# Clock_WR.net
KiCad netlist of a schematic drawn in Altium Designer
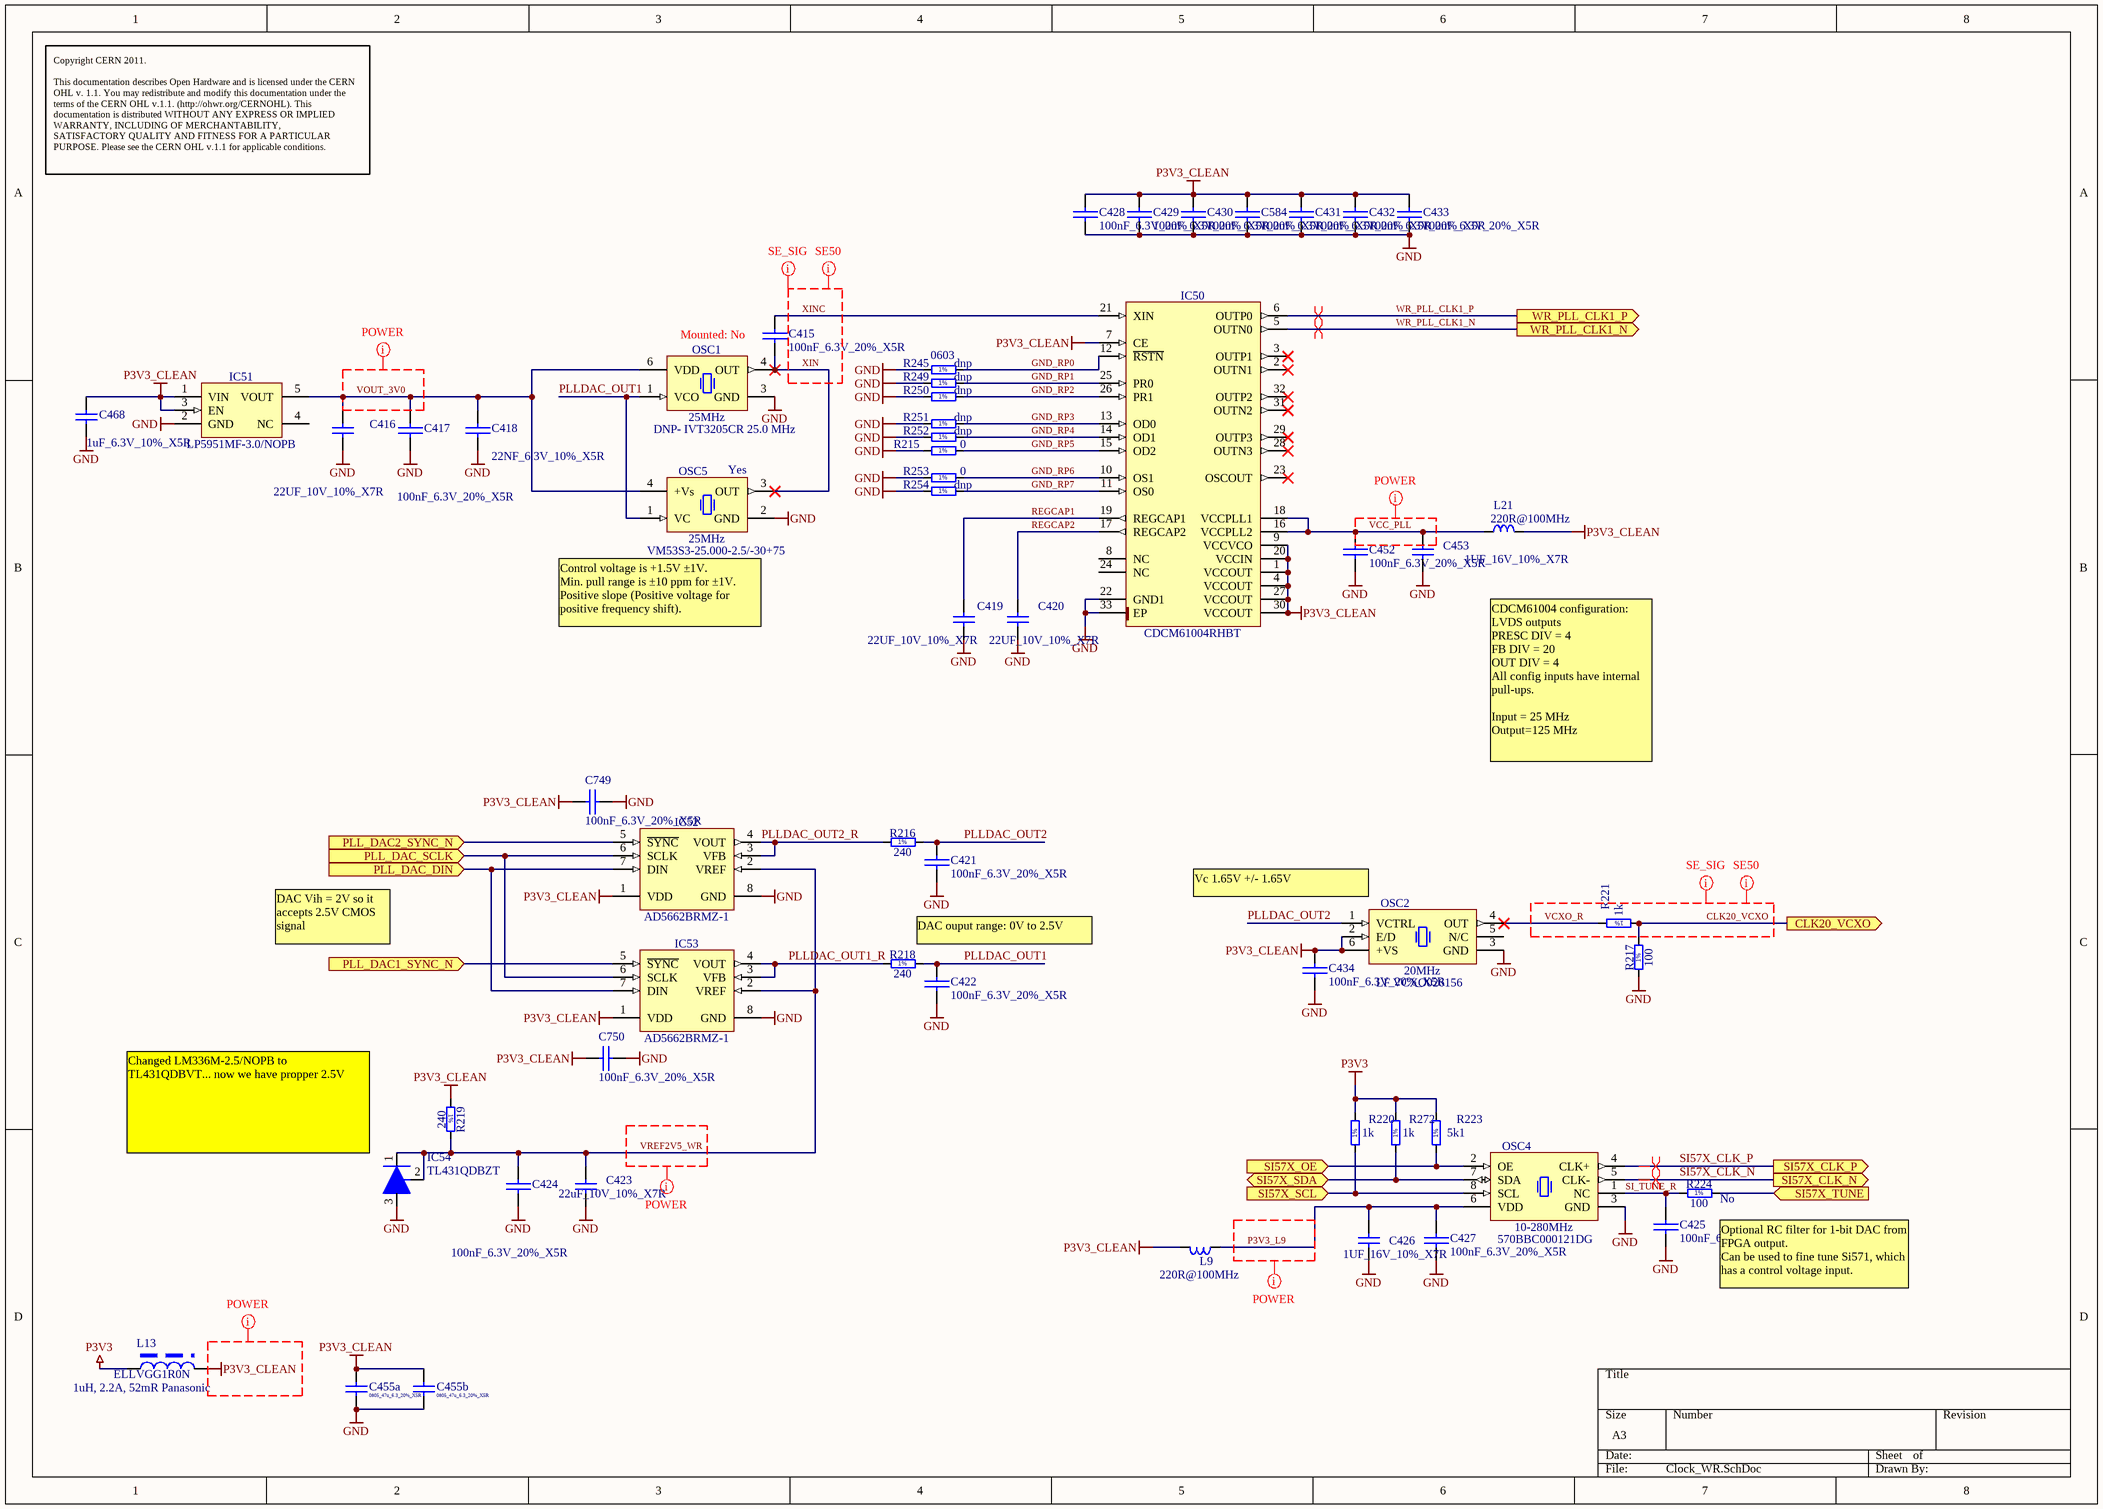
[diagram p0: Clock_WR.SchDoc]

(export (version "E")
  (design (tool "Eeschema 10.0.6"))
  (components
    (comp (ref "C415")
      (value "100nF_6.3V_20%_X5R")
      (footprint "0201C")
      (description "Capacitor SMD")
      (libsource (lib "LIBRARY_SCH") (part "CAP_SMD_0201"))
    )
    (comp (ref "C416")
      (value "22UF_10V_10%_X7R")
      (footprint "CAPC1608X87N")
      (description "Non-polarised capacitor")
      (fields
        (field (name "PART NUMBER") "CC0603_1UF_16V_10%_X7R")
        (field (name "VOLTAGE") "16V")
        (field (name "AUTHOR") "CERN DEM JLC")
      )
      (libsource (lib "Capacitors") (part "Capacitor - non polarized"))
    )
    (comp (ref "C417")
      (value "100nF_6.3V_20%_X5R")
      (footprint "0201C")
      (description "Capacitor SMD")
      (libsource (lib "LIBRARY_SCH") (part "CAP_SMD_0201"))
    )
    (comp (ref "C418")
      (value "22NF_6.3V_10%_X5R")
      (footprint "0201C")
      (description "Capacitor SMD")
      (libsource (lib "LIBRARY_SCH") (part "CAP_SMD_0201"))
    )
    (comp (ref "C419")
      (value "22UF_10V_10%_X7R")
      (footprint "CAPC3216X180N")
      (description "Non-polarised capacitor")
      (fields
        (field (name "PART NUMBER") "CC1206_22UF_10V_10%_X7R")
        (field (name "VOLTAGE") "10V")
        (field (name "AUTHOR") "CERN DEM JLC")
      )
      (libsource (lib "Capacitors") (part "Capacitor - non polarized"))
    )
    (comp (ref "C420")
      (value "22UF_10V_10%_X7R")
      (footprint "CAPC3216X180N")
      (description "Non-polarised capacitor")
      (fields
        (field (name "PART NUMBER") "CC1206_22UF_10V_10%_X7R")
        (field (name "VOLTAGE") "10V")
        (field (name "AUTHOR") "CERN DEM JLC")
      )
      (libsource (lib "Capacitors") (part "Capacitor - non polarized"))
    )
    (comp (ref "C421")
      (value "100nF_6.3V_20%_X5R")
      (footprint "0201C")
      (description "Capacitor SMD")
      (libsource (lib "LIBRARY_SCH") (part "CAP_SMD_0201"))
    )
    (comp (ref "C422")
      (value "100nF_6.3V_20%_X5R")
      (footprint "0201C")
      (description "Capacitor SMD")
      (libsource (lib "LIBRARY_SCH") (part "CAP_SMD_0201"))
    )
    (comp (ref "C423")
      (value "22uF_10V_10%_X7R")
      (footprint "CAPC3216X180N")
      (description "Non-polarised capacitor")
      (fields
        (field (name "PART NUMBER") "CC1206_22UF_10V_10%_X7R")
        (field (name "VOLTAGE") "10V")
        (field (name "AUTHOR") "CERN DEM JLC")
      )
      (libsource (lib "Capacitors") (part "Capacitor - non polarized"))
    )
    (comp (ref "C424")
      (value "100nF_6.3V_20%_X5R")
      (footprint "0201C")
      (description "Capacitor SMD")
      (libsource (lib "LIBRARY_SCH") (part "CAP_SMD_0201"))
    )
    (comp (ref "C425")
      (value "100nF_6.3V_20%_X5R")
      (footprint "0201C")
      (description "Capacitor SMD")
      (libsource (lib "LIBRARY_SCH") (part "CAP_SMD_0201"))
    )
    (comp (ref "C426")
      (value "1UF_16V_10%_X7R")
      (footprint "CAPC1608X87N")
      (description "Non-polarised capacitor")
      (fields
        (field (name "PART NUMBER") "CC0603_1UF_16V_10%_X7R")
        (field (name "VOLTAGE") "16V")
        (field (name "AUTHOR") "CERN DEM JLC")
      )
      (libsource (lib "Capacitors") (part "Capacitor - non polarized"))
    )
    (comp (ref "C427")
      (value "100nF_6.3V_20%_X5R")
      (footprint "0201C")
      (description "Capacitor SMD")
      (libsource (lib "LIBRARY_SCH") (part "CAP_SMD_0201"))
    )
    (comp (ref "C428")
      (value "100nF_6.3V_20%_X5R")
      (footprint "0201C")
      (description "Capacitor SMD")
      (libsource (lib "LIBRARY_SCH") (part "CAP_SMD_0201"))
    )
    (comp (ref "C429")
      (value "100nF_6.3V_20%_X5R")
      (footprint "0201C")
      (description "Capacitor SMD")
      (libsource (lib "LIBRARY_SCH") (part "CAP_SMD_0201"))
    )
    (comp (ref "C430")
      (value "100nF_6.3V_20%_X5R")
      (footprint "0201C")
      (description "Capacitor SMD")
      (libsource (lib "LIBRARY_SCH") (part "CAP_SMD_0201"))
    )
    (comp (ref "C431")
      (value "100nF_6.3V_20%_X5R")
      (footprint "0201C")
      (description "Capacitor SMD")
      (libsource (lib "LIBRARY_SCH") (part "CAP_SMD_0201"))
    )
    (comp (ref "C432")
      (value "100nF_6.3V_20%_X5R")
      (footprint "0201C")
      (description "Capacitor SMD")
      (libsource (lib "LIBRARY_SCH") (part "CAP_SMD_0201"))
    )
    (comp (ref "C433")
      (value "100nF_6.3V_20%_X5R")
      (footprint "0201C")
      (description "Capacitor SMD")
      (libsource (lib "LIBRARY_SCH") (part "CAP_SMD_0201"))
    )
    (comp (ref "C434")
      (value "100nF_6.3V_20%_X5R")
      (footprint "0201C")
      (description "Capacitor SMD")
      (libsource (lib "LIBRARY_SCH") (part "CAP_SMD_0201"))
    )
    (comp (ref "C452")
      (value "100nF_6.3V_20%_X5R")
      (footprint "0201C")
      (description "Capacitor SMD")
      (libsource (lib "LIBRARY_SCH") (part "CAP_SMD_0201"))
    )
    (comp (ref "C453")
      (value "1UF_16V_10%_X7R")
      (footprint "CAPC1608X87N")
      (description "Non-polarised capacitor")
      (fields
        (field (name "PART NUMBER") "CC0603_1UF_16V_10%_X7R")
        (field (name "VOLTAGE") "16V")
        (field (name "AUTHOR") "CERN DEM JLC")
      )
      (libsource (lib "Capacitors") (part "Capacitor - non polarized"))
    )
    (comp (ref "C455a")
      (value "0805_47u_6.3_20%_X5R")
      (footprint "CAPC2012X140N")
      (fields (field (name "PART NUMBER") "Ceramic_0805"))
      (libsource (lib "Capacitors") (part "Capacitor"))
    )
    (comp (ref "C455b")
      (value "0805_47u_6.3_20%_X5R")
      (footprint "CAPC2012X140N")
      (fields (field (name "PART NUMBER") "Ceramic_0805"))
      (libsource (lib "Capacitors") (part "Capacitor"))
    )
    (comp (ref "C468")
      (value "1uF_6.3V_10%_X5R")
      (footprint "CAPC1608X87N")
      (description "Non-polarised capacitor")
      (fields
        (field (name "PART NUMBER") "CC0603_1UF_16V_10%_X7R")
        (field (name "VOLTAGE") "16V")
        (field (name "AUTHOR") "CERN DEM JLC")
      )
      (libsource (lib "Capacitors") (part "Capacitor - non polarized"))
    )
    (comp (ref "C584")
      (value "100nF_6.3V_20%_X5R")
      (footprint "0201C")
      (description "Capacitor SMD")
      (libsource (lib "LIBRARY_SCH") (part "CAP_SMD_0201"))
    )
    (comp (ref "C749")
      (value "100nF_6.3V_20%_X5R")
      (footprint "0201C")
      (description "Capacitor SMD")
      (libsource (lib "LIBRARY_SCH") (part "CAP_SMD_0201"))
    )
    (comp (ref "C750")
      (value "100nF_6.3V_20%_X5R")
      (footprint "0201C")
      (description "Capacitor SMD")
      (libsource (lib "LIBRARY_SCH") (part "CAP_SMD_0201"))
    )
    (comp (ref "IC50")
      (value "CDCM61004RHBT")
      (footprint "QFN50P500X500X100-33N-S355")
      (description "Four Output, Integrated VCO, Low-Jitter Clock Generator")
      (fields (field (name "MANUFACTURER") "TEXAS INSTRUMENTS") (field (name "AUTHOR") "CERN DEM JLC"))
      (libsource (lib "ICs And Semiconductors") (part "CDCM61004RHB"))
    )
    (comp (ref "IC51")
      (value "LP5951MF-3.0/NOPB")
      (footprint "SOT95P284X122-5N")
      (description "150mA Micropower Low-Dropout CMOS Voltage Regulator")
      (fields (field (name "MANUFACTURER") "NATIONAL SEMICONDUCTOR") (field (name "AUTHOR") "CERN DEM JLC"))
      (libsource (lib "ICs And Semiconductors") (part "LP5951"))
    )
    (comp (ref "IC52")
      (value "AD5662BRMZ-1")
      (footprint "SOP65P490X110-8N")
      (description "2.7V to 5.5V, 250uA, Rail-to-Rail Output 16-Bit nanoDAC")
      (fields (field (name "MANUFACTURER") "ANALOG DEVICES") (field (name "AUTHOR") "CERN DEM JLC"))
      (libsource (lib "ICs And Semiconductors") (part "AD5662"))
    )
    (comp (ref "IC53")
      (value "AD5662BRMZ-1")
      (footprint "SOP65P490X110-8N")
      (description "2.7V to 5.5V, 250uA, Rail-to-Rail Output 16-Bit nanoDAC")
      (fields (field (name "MANUFACTURER") "ANALOG DEVICES") (field (name "AUTHOR") "CERN DEM JLC"))
      (libsource (lib "ICs And Semiconductors") (part "AD5662"))
    )
    (comp (ref "IC54")
      (value "TL431QDBZT")
      (footprint "SOT-23")
      (description "2.5V ADJ Voltage reference")
      (libsource (lib "LIBRARY_SCH") (part "REF_TL431_SOT23"))
    )
    (comp (ref "L9")
      (value "220R@100MHz")
      (footprint "INDC2012X105N")
      (description "Inductor")
      (fields
        (field (name "PART NUMBER") "IND0805_MURATA_BLM21PG221SN1D")
        (field (name "POWER") "2A")
        (field (name "AUTHOR") "CERN DEM JLC")
      )
      (libsource (lib "Inductors & Transformers") (part "Inductor"))
    )
    (comp (ref "L13")
      (value "ELLVGG1R0N")
      (footprint "L_ELLVGG2R2N")
      (description "2.2uH, 1.4A, 92mR Panasonic")
      (fields (field (name "ALTIUM_UNNAMED_1") "1uH, 2.2A, 52mR Panasonic"))
      (libsource (lib "LIBRARY_SCH") (part "L_CHOKE_ELLVGG"))
    )
    (comp (ref "L21")
      (value "220R@100MHz")
      (footprint "INDC2012X105N")
      (description "Inductor")
      (fields
        (field (name "PART NUMBER") "IND0805_MURATA_BLM21PG221SN1D")
        (field (name "POWER") "2A")
        (field (name "AUTHOR") "CERN DEM JLC")
      )
      (libsource (lib "Inductors & Transformers") (part "Inductor"))
    )
    (comp (ref "OSC1")
      (value "25MHz")
      (footprint "OSC_RAKON_IVT3200C")
      (description "Oscillator 4 pins 1=VCO 3=GND 4=OUT 6=VDC")
      (fields
        (field (name "PART NUMBER") "OSC_25MHZ_RAKON_IVT3205CR")
        (field (name "MANUFACTURER") "RAKON")
        (field (name "MANUFACTURER PART NUMBER") "DNP- IVT3205CR 25.0 MHz")
        (field (name "MOUNTED") "No")
        (field (name "AUTHOR") "CERN DEM JLC")
      )
      (libsource (lib "ICs And Semiconductors") (part "Oscillator 1VCO 3GND 4OUT 6VCC"))
    )
    (comp (ref "OSC2")
      (value "20MHz")
      (footprint "OSC_IQD_CFPV-45")
      (description "3.3V ±100ppm 15pF HCMOS Tri-State Surface Mount Voltage Controlled Oscillator VCXO (CFPV-45 Serie)")
      (fields
        (field (name "PART NUMBER") "OSC_20MHZ_IQD_LF VCXO026156")
        (field (name "MANUFACTURER") "IQD FREQUENCY PRODUCTS")
        (field (name "MANUFACTURER PART NUMBER") "LF VCXO026156")
        (field (name "AUTHOR") "CERN DEM JLC")
      )
      (libsource (lib "ICs And Semiconductors") (part "Oscillator IQD_CFPV-45"))
    )
    (comp (ref "OSC4")
      (value "10-280MHz")
      (footprint "OSC_SILICON-LAB_SI570")
      (description "Any-Rate I2C Programmable XO Oscillator Si570 Serie")
      (fields
        (field (name "PART NUMBER") "OSC_10-280MHZ_SILICON-LAB_Si570BBC000121DG")
        (field (name "MANUFACTURER") "SILICON LABS")
        (field (name "MANUFACTURER PART NUMBER") "570BBC000121DG")
        (field (name "AUTHOR") "CERN DEM JLC")
      )
      (libsource (lib "ICs And Semiconductors") (part "Oscillator SILICON-LAB_Si570"))
    )
    (comp (ref "OSC5")
      (value "25MHz")
      (footprint "OSCCC320X500X160-4N")
      (description "Oscillator 4 pins 1=VC 2=GND 3=OUT 4=+Vs")
      (fields
        (field (name "PART NUMBER") "OSC_25MHZ_MERCURY_VM53S3-25.000-2.5/-30+75")
        (field (name "MANUFACTURER") "MERCURY ELECTRONICS")
        (field (name "MANUFACTURER PART NUMBER") "VM53S3-25.000-2.5/-30+75")
        (field (name "MOUNTED") "Yes")
        (field (name "AUTHOR") "CERN DEM JLC")
      )
      (libsource (lib "ICs And Semiconductors") (part "Oscillator 1VC 2GND 3OUT 4+Vs"))
    )
    (comp (ref "R215")
      (value "0")
      (footprint "RESC1608X55N")
      (description "Resistor - 1%")
      (fields
        (field (name "PART NUMBER") "R0603_0R_JUMPER")
        (field (name "MANUFACTURER") "GENERIC")
        (field (name "AUTHOR") "CERN DEM JLC")
      )
      (libsource (lib "Resistors") (part "Resistor - 1%"))
    )
    (comp (ref "R216")
      (value "240")
      (footprint "RESC1608X55N")
      (description "Resistor - 1%")
      (fields
        (field (name "PART NUMBER") "R0603_240R_1%_0.1W_100PPM")
        (field (name "POWER") "0.1W")
        (field (name "AUTHOR") "CERN DEM JLC")
      )
      (libsource (lib "Resistors") (part "Resistor - 1%"))
    )
    (comp (ref "R217")
      (value "100")
      (footprint "RESC1608X55N")
      (description "Resistor - 1%")
      (fields
        (field (name "PART NUMBER") "R0603_100R_1%_0.1W_100PPM")
        (field (name "POWER") "0.1W")
        (field (name "AUTHOR") "CERN DEM JLC")
      )
      (libsource (lib "Resistors") (part "Resistor - 1%"))
    )
    (comp (ref "R218")
      (value "240")
      (footprint "RESC1608X55N")
      (description "Resistor - 1%")
      (fields
        (field (name "PART NUMBER") "R0603_240R_1%_0.1W_100PPM")
        (field (name "POWER") "0.1W")
        (field (name "AUTHOR") "CERN DEM JLC")
      )
      (libsource (lib "Resistors") (part "Resistor - 1%"))
    )
    (comp (ref "R219")
      (value "240")
      (footprint "RESC1608X55N")
      (description "Resistor - 1%")
      (fields
        (field (name "PART NUMBER") "R0603_240R_1%_0.1W_100PPM")
        (field (name "POWER") "0.1W")
        (field (name "AUTHOR") "CERN DEM JLC")
      )
      (libsource (lib "Resistors") (part "Resistor - 1%"))
    )
    (comp (ref "R220")
      (value "1k")
      (footprint "RESC1608X55N")
      (description "Resistor - 1%")
      (fields
        (field (name "PART NUMBER") "R0603_1K_1%_0.1W_100PPM")
        (field (name "POWER") "0.1W")
        (field (name "AUTHOR") "CERN DEM JLC")
      )
      (libsource (lib "Resistors") (part "Resistor - 1%"))
    )
    (comp (ref "R221")
      (value "1k")
      (footprint "RESC1608X55N")
      (description "Resistor - 1%")
      (fields
        (field (name "PART NUMBER") "R0603_1K_1%_0.1W_100PPM")
        (field (name "POWER") "0.1W")
        (field (name "AUTHOR") "CERN DEM JLC")
      )
      (libsource (lib "Resistors") (part "Resistor - 1%"))
    )
    (comp (ref "R223")
      (value "5k1")
      (footprint "RESC1608X55N")
      (description "Resistor - 1%")
      (fields
        (field (name "PART NUMBER") "R0603_5K1_1%_0.1W_100PPM")
        (field (name "POWER") "0.1W")
        (field (name "AUTHOR") "CERN DEM JLC")
      )
      (libsource (lib "Resistors") (part "Resistor - 1%"))
    )
    (comp (ref "R224")
      (value "100")
      (footprint "RESC1608X55N")
      (description "Resistor - 1%")
      (fields
        (field (name "PART NUMBER") "R0603_100R_1%_0.1W_100PPM")
        (field (name "POWER") "0.1W")
        (field (name "MOUNTED") "No")
        (field (name "AUTHOR") "CERN DEM JLC")
      )
      (libsource (lib "Resistors") (part "Resistor - 1%"))
    )
    (comp (ref "R245")
      (value "dnp")
      (footprint "RESC1608X55N")
      (description "Resistor - 1%")
      (fields
        (field (name "PART NUMBER") "R0603_0R_JUMPER")
        (field (name "MANUFACTURER") "GENERIC")
        (field (name "CASE") "0603")
        (field (name "AUTHOR") "CERN DEM JLC")
      )
      (libsource (lib "Resistors") (part "Resistor - 1%"))
    )
    (comp (ref "R249")
      (value "dnp")
      (footprint "RESC1608X55N")
      (description "Resistor - 1%")
      (fields
        (field (name "PART NUMBER") "R0603_0R_JUMPER")
        (field (name "MANUFACTURER") "GENERIC")
        (field (name "AUTHOR") "CERN DEM JLC")
      )
      (libsource (lib "Resistors") (part "Resistor - 1%"))
    )
    (comp (ref "R250")
      (value "dnp")
      (footprint "RESC1608X55N")
      (description "Resistor - 1%")
      (fields
        (field (name "PART NUMBER") "R0603_0R_JUMPER")
        (field (name "MANUFACTURER") "GENERIC")
        (field (name "AUTHOR") "CERN DEM JLC")
      )
      (libsource (lib "Resistors") (part "Resistor - 1%"))
    )
    (comp (ref "R251")
      (value "dnp")
      (footprint "RESC1608X55N")
      (description "Resistor - 1%")
      (fields
        (field (name "PART NUMBER") "R0603_0R_JUMPER")
        (field (name "MANUFACTURER") "GENERIC")
        (field (name "AUTHOR") "CERN DEM JLC")
      )
      (libsource (lib "Resistors") (part "Resistor - 1%"))
    )
    (comp (ref "R252")
      (value "dnp")
      (footprint "RESC1608X55N")
      (description "Resistor - 1%")
      (fields
        (field (name "PART NUMBER") "R0603_0R_JUMPER")
        (field (name "MANUFACTURER") "GENERIC")
        (field (name "AUTHOR") "CERN DEM JLC")
      )
      (libsource (lib "Resistors") (part "Resistor - 1%"))
    )
    (comp (ref "R253")
      (value "0")
      (footprint "RESC1608X55N")
      (description "Resistor - 1%")
      (fields
        (field (name "PART NUMBER") "R0603_0R_JUMPER")
        (field (name "MANUFACTURER") "GENERIC")
        (field (name "AUTHOR") "CERN DEM JLC")
      )
      (libsource (lib "Resistors") (part "Resistor - 1%"))
    )
    (comp (ref "R254")
      (value "dnp")
      (footprint "RESC1608X55N")
      (description "Resistor - 1%")
      (fields
        (field (name "PART NUMBER") "R0603_0R_JUMPER")
        (field (name "MANUFACTURER") "GENERIC")
        (field (name "AUTHOR") "CERN DEM JLC")
      )
      (libsource (lib "Resistors") (part "Resistor - 1%"))
    )
    (comp (ref "R272")
      (value "1k")
      (footprint "RESC1608X55N")
      (description "Resistor - 1%")
      (fields
        (field (name "PART NUMBER") "R0603_1K_1%_0.1W_100PPM")
        (field (name "POWER") "0.1W")
        (field (name "AUTHOR") "CERN DEM JLC")
      )
      (libsource (lib "Resistors") (part "Resistor - 1%"))
    )
  )
  (nets
    (net (code "1") (name "/CLK20_VCXO") (class "Default")
      (node (ref "R217") (pin "2") (pinfunction "2_2") (pintype "passive"))
      (node (ref "R221") (pin "1") (pinfunction "1_1") (pintype "passive"))
    )
    (net (code "2") (name "/GND_RP0") (class "Default")
      (node (ref "IC50") (pin "12") (pinfunction "~{RSTN}_12") (pintype "input"))
      (node (ref "R245") (pin "2") (pinfunction "2_2") (pintype "passive"))
    )
    (net (code "3") (name "/GND_RP1") (class "Default")
      (node (ref "IC50") (pin "25") (pinfunction "PR0_25") (pintype "input"))
      (node (ref "R249") (pin "2") (pinfunction "2_2") (pintype "passive"))
    )
    (net (code "4") (name "/GND_RP2") (class "Default")
      (node (ref "IC50") (pin "26") (pinfunction "PR1_26") (pintype "input"))
      (node (ref "R250") (pin "2") (pinfunction "2_2") (pintype "passive"))
    )
    (net (code "5") (name "/GND_RP3") (class "Default")
      (node (ref "IC50") (pin "13") (pinfunction "OD0_13") (pintype "input"))
      (node (ref "R251") (pin "2") (pinfunction "2_2") (pintype "passive"))
    )
    (net (code "6") (name "/GND_RP4") (class "Default")
      (node (ref "IC50") (pin "14") (pinfunction "OD1_14") (pintype "input"))
      (node (ref "R252") (pin "2") (pinfunction "2_2") (pintype "passive"))
    )
    (net (code "7") (name "/GND_RP5") (class "Default")
      (node (ref "IC50") (pin "15") (pinfunction "OD2_15") (pintype "input"))
      (node (ref "R215") (pin "2") (pinfunction "2_2") (pintype "passive"))
    )
    (net (code "8") (name "/GND_RP6") (class "Default")
      (node (ref "IC50") (pin "10") (pinfunction "OS1_10") (pintype "input"))
      (node (ref "R253") (pin "2") (pinfunction "2_2") (pintype "passive"))
    )
    (net (code "9") (name "/GND_RP7") (class "Default")
      (node (ref "IC50") (pin "11") (pinfunction "OS0_11") (pintype "input"))
      (node (ref "R254") (pin "2") (pinfunction "2_2") (pintype "passive"))
    )
    (net (code "10") (name "/P3V3_L9") (class "Default")
      (node (ref "C426") (pin "2") (pinfunction "2_2") (pintype "passive"))
      (node (ref "C427") (pin "1") (pinfunction "1_1") (pintype "passive"))
      (node (ref "L9") (pin "1") (pinfunction "1_1") (pintype "passive"))
      (node (ref "OSC4") (pin "6") (pinfunction "VDD_6") (pintype "power_in"))
    )
    (net (code "11") (name "/PLLDAC_OUT1") (class "Default")
      (node (ref "C422") (pin "1") (pinfunction "1_1") (pintype "passive"))
      (node (ref "OSC1") (pin "1") (pinfunction "VCO_1") (pintype "input"))
      (node (ref "OSC5") (pin "1") (pinfunction "VC_1") (pintype "input"))
      (node (ref "R218") (pin "2") (pinfunction "2_2") (pintype "passive"))
    )
    (net (code "12") (name "/PLLDAC_OUT1_R") (class "Default")
      (node (ref "IC53") (pin "3") (pinfunction "VFB_3") (pintype "input"))
      (node (ref "IC53") (pin "4") (pinfunction "VOUT_4") (pintype "output"))
      (node (ref "R218") (pin "1") (pinfunction "1_1") (pintype "passive"))
    )
    (net (code "13") (name "/PLLDAC_OUT2") (class "Default")
      (node (ref "C421") (pin "1") (pinfunction "1_1") (pintype "passive"))
      (node (ref "OSC2") (pin "1") (pinfunction "VCTRL_1") (pintype "input"))
      (node (ref "R216") (pin "2") (pinfunction "2_2") (pintype "passive"))
    )
    (net (code "14") (name "/PLLDAC_OUT2_R") (class "Default")
      (node (ref "IC52") (pin "3") (pinfunction "VFB_3") (pintype "input"))
      (node (ref "IC52") (pin "4") (pinfunction "VOUT_4") (pintype "output"))
      (node (ref "R216") (pin "1") (pinfunction "1_1") (pintype "passive"))
    )
    (net (code "15") (name "/PLL_DAC1_SYNC_N") (class "Default")
      (node (ref "IC53") (pin "5") (pinfunction "~{SYNC}_5") (pintype "input"))
    )
    (net (code "16") (name "/PLL_DAC2_SYNC_N") (class "Default")
      (node (ref "IC52") (pin "5") (pinfunction "~{SYNC}_5") (pintype "input"))
    )
    (net (code "17") (name "/PLL_DAC_DIN") (class "Default")
      (node (ref "IC52") (pin "7") (pinfunction "DIN_7") (pintype "input"))
      (node (ref "IC53") (pin "7") (pinfunction "DIN_7") (pintype "input"))
    )
    (net (code "18") (name "/PLL_DAC_SCLK") (class "Default")
      (node (ref "IC52") (pin "6") (pinfunction "SCLK_6") (pintype "input"))
      (node (ref "IC53") (pin "6") (pinfunction "SCLK_6") (pintype "input"))
    )
    (net (code "19") (name "/REGCAP1") (class "Default")
      (node (ref "C419") (pin "2") (pinfunction "2_2") (pintype "passive"))
      (node (ref "IC50") (pin "19") (pinfunction "REGCAP1_19") (pintype "output"))
    )
    (net (code "20") (name "/REGCAP2") (class "Default")
      (node (ref "C420") (pin "2") (pinfunction "2_2") (pintype "passive"))
      (node (ref "IC50") (pin "17") (pinfunction "REGCAP2_17") (pintype "output"))
    )
    (net (code "21") (name "/SI57X_CLK_N") (class "Default")
      (node (ref "OSC4") (pin "5") (pinfunction "CLK-_5") (pintype "output"))
    )
    (net (code "22") (name "/SI57X_CLK_P") (class "Default")
      (node (ref "OSC4") (pin "4") (pinfunction "CLK+_4") (pintype "output"))
    )
    (net (code "23") (name "/SI57X_OE") (class "Default")
      (node (ref "OSC4") (pin "2") (pinfunction "OE_2") (pintype "input"))
      (node (ref "R223") (pin "1") (pinfunction "1_1") (pintype "passive"))
    )
    (net (code "24") (name "/SI57X_SCL") (class "Default")
      (node (ref "OSC4") (pin "8") (pinfunction "SCL_8") (pintype "input"))
      (node (ref "R220") (pin "1") (pinfunction "1_1") (pintype "passive"))
    )
    (net (code "25") (name "/SI57X_SDA") (class "Default")
      (node (ref "OSC4") (pin "7") (pinfunction "SDA_7") (pintype "bidirectional"))
      (node (ref "R272") (pin "1") (pinfunction "1_1") (pintype "passive"))
    )
    (net (code "26") (name "/SI57X_TUNE") (class "Default")
      (node (ref "R224") (pin "2") (pinfunction "2_2") (pintype "passive"))
    )
    (net (code "27") (name "/SI_TUNE_R") (class "Default")
      (node (ref "C425") (pin "1") (pinfunction "1_1") (pintype "passive"))
      (node (ref "OSC4") (pin "1") (pinfunction "NC_1") (pintype "passive"))
      (node (ref "R224") (pin "1") (pinfunction "1_1") (pintype "passive"))
    )
    (net (code "28") (name "/VCC_PLL") (class "Default")
      (node (ref "C452") (pin "1") (pinfunction "1_1") (pintype "passive"))
      (node (ref "C453") (pin "2") (pinfunction "2_2") (pintype "passive"))
      (node (ref "IC50") (pin "16") (pinfunction "VCCPLL2_16") (pintype "power_in"))
      (node (ref "IC50") (pin "18") (pinfunction "VCCPLL1_18") (pintype "power_in"))
      (node (ref "L21") (pin "1") (pinfunction "1_1") (pintype "passive"))
    )
    (net (code "29") (name "/VCXO_R") (class "Default")
      (node (ref "OSC2") (pin "4") (pinfunction "OUT_4") (pintype "output"))
      (node (ref "R221") (pin "2") (pinfunction "2_2") (pintype "passive"))
    )
    (net (code "30") (name "/VOUT_3V0") (class "Default")
      (node (ref "C416") (pin "2") (pinfunction "2_2") (pintype "passive"))
      (node (ref "C417") (pin "1") (pinfunction "1_1") (pintype "passive"))
      (node (ref "C418") (pin "2") (pinfunction "2_2") (pintype "passive"))
      (node (ref "IC51") (pin "5") (pinfunction "VOUT_5") (pintype "power_in"))
      (node (ref "OSC1") (pin "6") (pinfunction "VDD_6") (pintype "power_in"))
      (node (ref "OSC5") (pin "4") (pinfunction "+Vs_4") (pintype "power_in"))
    )
    (net (code "31") (name "/VREF2V5_WR") (class "Default")
      (node (ref "C423") (pin "2") (pinfunction "2_2") (pintype "passive"))
      (node (ref "C424") (pin "1") (pinfunction "1_1") (pintype "passive"))
      (node (ref "IC52") (pin "2") (pinfunction "VREF_2") (pintype "input"))
      (node (ref "IC53") (pin "2") (pinfunction "VREF_2") (pintype "input"))
      (node (ref "IC54") (pin "1") (pinfunction "I/O_1") (pintype "passive"))
      (node (ref "IC54") (pin "2") (pinfunction "REF_2") (pintype "passive"))
      (node (ref "R219") (pin "2") (pinfunction "2_2") (pintype "passive"))
    )
    (net (code "32") (name "/WR_PLL_CLK1_N") (class "Default")
      (node (ref "IC50") (pin "5") (pinfunction "OUTN0_5") (pintype "output"))
    )
    (net (code "33") (name "/WR_PLL_CLK1_P") (class "Default")
      (node (ref "IC50") (pin "6") (pinfunction "OUTP0_6") (pintype "output"))
    )
    (net (code "34") (name "/XIN") (class "Default")
      (node (ref "C415") (pin "1") (pinfunction "1_1") (pintype "passive"))
      (node (ref "OSC1") (pin "4") (pinfunction "OUT_4") (pintype "output"))
      (node (ref "OSC5") (pin "3") (pinfunction "OUT_3") (pintype "output"))
    )
    (net (code "35") (name "/XINC") (class "Default")
      (node (ref "C415") (pin "2") (pinfunction "2_2") (pintype "passive"))
      (node (ref "IC50") (pin "21") (pinfunction "XIN_21") (pintype "input"))
    )
    (net (code "36") (name "GND") (class "Default")
      (node (ref "C416") (pin "1") (pinfunction "1_1") (pintype "passive"))
      (node (ref "C417") (pin "2") (pinfunction "2_2") (pintype "passive"))
      (node (ref "C418") (pin "1") (pinfunction "1_1") (pintype "passive"))
      (node (ref "C419") (pin "1") (pinfunction "1_1") (pintype "passive"))
      (node (ref "C420") (pin "1") (pinfunction "1_1") (pintype "passive"))
      (node (ref "C421") (pin "2") (pinfunction "2_2") (pintype "passive"))
      (node (ref "C422") (pin "2") (pinfunction "2_2") (pintype "passive"))
      (node (ref "C423") (pin "1") (pinfunction "1_1") (pintype "passive"))
      (node (ref "C424") (pin "2") (pinfunction "2_2") (pintype "passive"))
      (node (ref "C425") (pin "2") (pinfunction "2_2") (pintype "passive"))
      (node (ref "C426") (pin "1") (pinfunction "1_1") (pintype "passive"))
      (node (ref "C427") (pin "2") (pinfunction "2_2") (pintype "passive"))
      (node (ref "C428") (pin "1") (pinfunction "1_1") (pintype "passive"))
      (node (ref "C429") (pin "2") (pinfunction "2_2") (pintype "passive"))
      (node (ref "C430") (pin "2") (pinfunction "2_2") (pintype "passive"))
      (node (ref "C431") (pin "2") (pinfunction "2_2") (pintype "passive"))
      (node (ref "C432") (pin "2") (pinfunction "2_2") (pintype "passive"))
      (node (ref "C433") (pin "2") (pinfunction "2_2") (pintype "passive"))
      (node (ref "C434") (pin "2") (pinfunction "2_2") (pintype "passive"))
      (node (ref "C452") (pin "2") (pinfunction "2_2") (pintype "passive"))
      (node (ref "C453") (pin "1") (pinfunction "1_1") (pintype "passive"))
      (node (ref "C455a") (pin "1") (pinfunction "1_1") (pintype "passive"))
      (node (ref "C455b") (pin "1") (pinfunction "1_1") (pintype "passive"))
      (node (ref "C468") (pin "1") (pinfunction "1_1") (pintype "passive"))
      (node (ref "C584") (pin "2") (pinfunction "2_2") (pintype "passive"))
      (node (ref "C749") (pin "2") (pinfunction "2_2") (pintype "passive"))
      (node (ref "C750") (pin "2") (pinfunction "2_2") (pintype "passive"))
      (node (ref "IC50") (pin "22") (pinfunction "GND1_22") (pintype "power_in"))
      (node (ref "IC50") (pin "33") (pinfunction "EP_33") (pintype "power_in"))
      (node (ref "IC51") (pin "2") (pinfunction "GND_2") (pintype "power_in"))
      (node (ref "IC52") (pin "8") (pinfunction "GND_8") (pintype "power_in"))
      (node (ref "IC53") (pin "8") (pinfunction "GND_8") (pintype "power_in"))
      (node (ref "IC54") (pin "3") (pinfunction "A_3") (pintype "passive"))
      (node (ref "OSC1") (pin "3") (pinfunction "GND_3") (pintype "power_in"))
      (node (ref "OSC2") (pin "3") (pinfunction "GND_3") (pintype "power_in"))
      (node (ref "OSC4") (pin "3") (pinfunction "GND_3") (pintype "power_in"))
      (node (ref "OSC5") (pin "2") (pinfunction "GND_2") (pintype "power_in"))
      (node (ref "R215") (pin "1") (pinfunction "1_1") (pintype "passive"))
      (node (ref "R217") (pin "1") (pinfunction "1_1") (pintype "passive"))
      (node (ref "R245") (pin "1") (pinfunction "1_1") (pintype "passive"))
      (node (ref "R249") (pin "1") (pinfunction "1_1") (pintype "passive"))
      (node (ref "R250") (pin "1") (pinfunction "1_1") (pintype "passive"))
      (node (ref "R251") (pin "1") (pinfunction "1_1") (pintype "passive"))
      (node (ref "R252") (pin "1") (pinfunction "1_1") (pintype "passive"))
      (node (ref "R253") (pin "1") (pinfunction "1_1") (pintype "passive"))
      (node (ref "R254") (pin "1") (pinfunction "1_1") (pintype "passive"))
    )
    (net (code "37") (name "P3V3") (class "Default")
      (node (ref "L13") (pin "1") (pintype "passive"))
      (node (ref "R220") (pin "2") (pinfunction "2_2") (pintype "passive"))
      (node (ref "R223") (pin "2") (pinfunction "2_2") (pintype "passive"))
      (node (ref "R272") (pin "2") (pinfunction "2_2") (pintype "passive"))
    )
    (net (code "38") (name "P3V3_CLEAN") (class "Default")
      (node (ref "C428") (pin "2") (pinfunction "2_2") (pintype "passive"))
      (node (ref "C429") (pin "1") (pinfunction "1_1") (pintype "passive"))
      (node (ref "C430") (pin "1") (pinfunction "1_1") (pintype "passive"))
      (node (ref "C431") (pin "1") (pinfunction "1_1") (pintype "passive"))
      (node (ref "C432") (pin "1") (pinfunction "1_1") (pintype "passive"))
      (node (ref "C433") (pin "1") (pinfunction "1_1") (pintype "passive"))
      (node (ref "C434") (pin "1") (pinfunction "1_1") (pintype "passive"))
      (node (ref "C455a") (pin "2") (pinfunction "2_2") (pintype "passive"))
      (node (ref "C455b") (pin "2") (pinfunction "2_2") (pintype "passive"))
      (node (ref "C468") (pin "2") (pinfunction "2_2") (pintype "passive"))
      (node (ref "C584") (pin "1") (pinfunction "1_1") (pintype "passive"))
      (node (ref "C749") (pin "1") (pinfunction "1_1") (pintype "passive"))
      (node (ref "C750") (pin "1") (pinfunction "1_1") (pintype "passive"))
      (node (ref "IC50") (pin "1") (pinfunction "VCCOUT_1") (pintype "power_in"))
      (node (ref "IC50") (pin "20") (pinfunction "VCCIN_20") (pintype "power_in"))
      (node (ref "IC50") (pin "27") (pinfunction "VCCOUT_27") (pintype "power_in"))
      (node (ref "IC50") (pin "30") (pinfunction "VCCOUT_30") (pintype "power_in"))
      (node (ref "IC50") (pin "4") (pinfunction "VCCOUT_4") (pintype "power_in"))
      (node (ref "IC50") (pin "7") (pinfunction "CE_7") (pintype "input"))
      (node (ref "IC50") (pin "9") (pinfunction "VCCVCO_9") (pintype "power_in"))
      (node (ref "IC51") (pin "1") (pinfunction "VIN_1") (pintype "power_in"))
      (node (ref "IC51") (pin "3") (pinfunction "EN_3") (pintype "input"))
      (node (ref "IC52") (pin "1") (pinfunction "VDD_1") (pintype "power_in"))
      (node (ref "IC53") (pin "1") (pinfunction "VDD_1") (pintype "power_in"))
      (node (ref "L13") (pin "2") (pintype "passive"))
      (node (ref "L21") (pin "2") (pinfunction "2_2") (pintype "passive"))
      (node (ref "L9") (pin "2") (pinfunction "2_2") (pintype "passive"))
      (node (ref "OSC2") (pin "2") (pinfunction "E/D_2") (pintype "input"))
      (node (ref "OSC2") (pin "6") (pinfunction "+VS_6") (pintype "power_in"))
      (node (ref "R219") (pin "1") (pinfunction "1_1") (pintype "passive"))
    )
    (net (code "39") (name "unconnected-(IC50-NC-Pad8)") (class "Default")
      (node (ref "IC50") (pin "8") (pinfunction "NC_8") (pintype "passive"))
    )
    (net (code "40") (name "unconnected-(IC50-NC-Pad24)") (class "Default")
      (node (ref "IC50") (pin "24") (pinfunction "NC_24") (pintype "passive"))
    )
    (net (code "41") (name "unconnected-(IC50-OSCOUT-Pad23)") (class "Default")
      (node (ref "IC50") (pin "23") (pinfunction "OSCOUT_23") (pintype "output+no_connect"))
    )
    (net (code "42") (name "unconnected-(IC50-OUTN1-Pad2)") (class "Default")
      (node (ref "IC50") (pin "2") (pinfunction "OUTN1_2") (pintype "output+no_connect"))
    )
    (net (code "43") (name "unconnected-(IC50-OUTN2-Pad31)") (class "Default")
      (node (ref "IC50") (pin "31") (pinfunction "OUTN2_31") (pintype "output+no_connect"))
    )
    (net (code "44") (name "unconnected-(IC50-OUTN3-Pad28)") (class "Default")
      (node (ref "IC50") (pin "28") (pinfunction "OUTN3_28") (pintype "output+no_connect"))
    )
    (net (code "45") (name "unconnected-(IC50-OUTP1-Pad3)") (class "Default")
      (node (ref "IC50") (pin "3") (pinfunction "OUTP1_3") (pintype "output+no_connect"))
    )
    (net (code "46") (name "unconnected-(IC50-OUTP2-Pad32)") (class "Default")
      (node (ref "IC50") (pin "32") (pinfunction "OUTP2_32") (pintype "output+no_connect"))
    )
    (net (code "47") (name "unconnected-(IC50-OUTP3-Pad29)") (class "Default")
      (node (ref "IC50") (pin "29") (pinfunction "OUTP3_29") (pintype "output+no_connect"))
    )
    (net (code "48") (name "unconnected-(IC51-NC-Pad4)") (class "Default")
      (node (ref "IC51") (pin "4") (pinfunction "NC_4") (pintype "passive"))
    )
    (net (code "49") (name "unconnected-(OSC2-N{slash}C-Pad5)") (class "Default")
      (node (ref "OSC2") (pin "5") (pinfunction "N/C_5") (pintype "passive"))
    )
  )
)
